# progduino.net
KiCad netlist of a schematic drawn in EAGLE
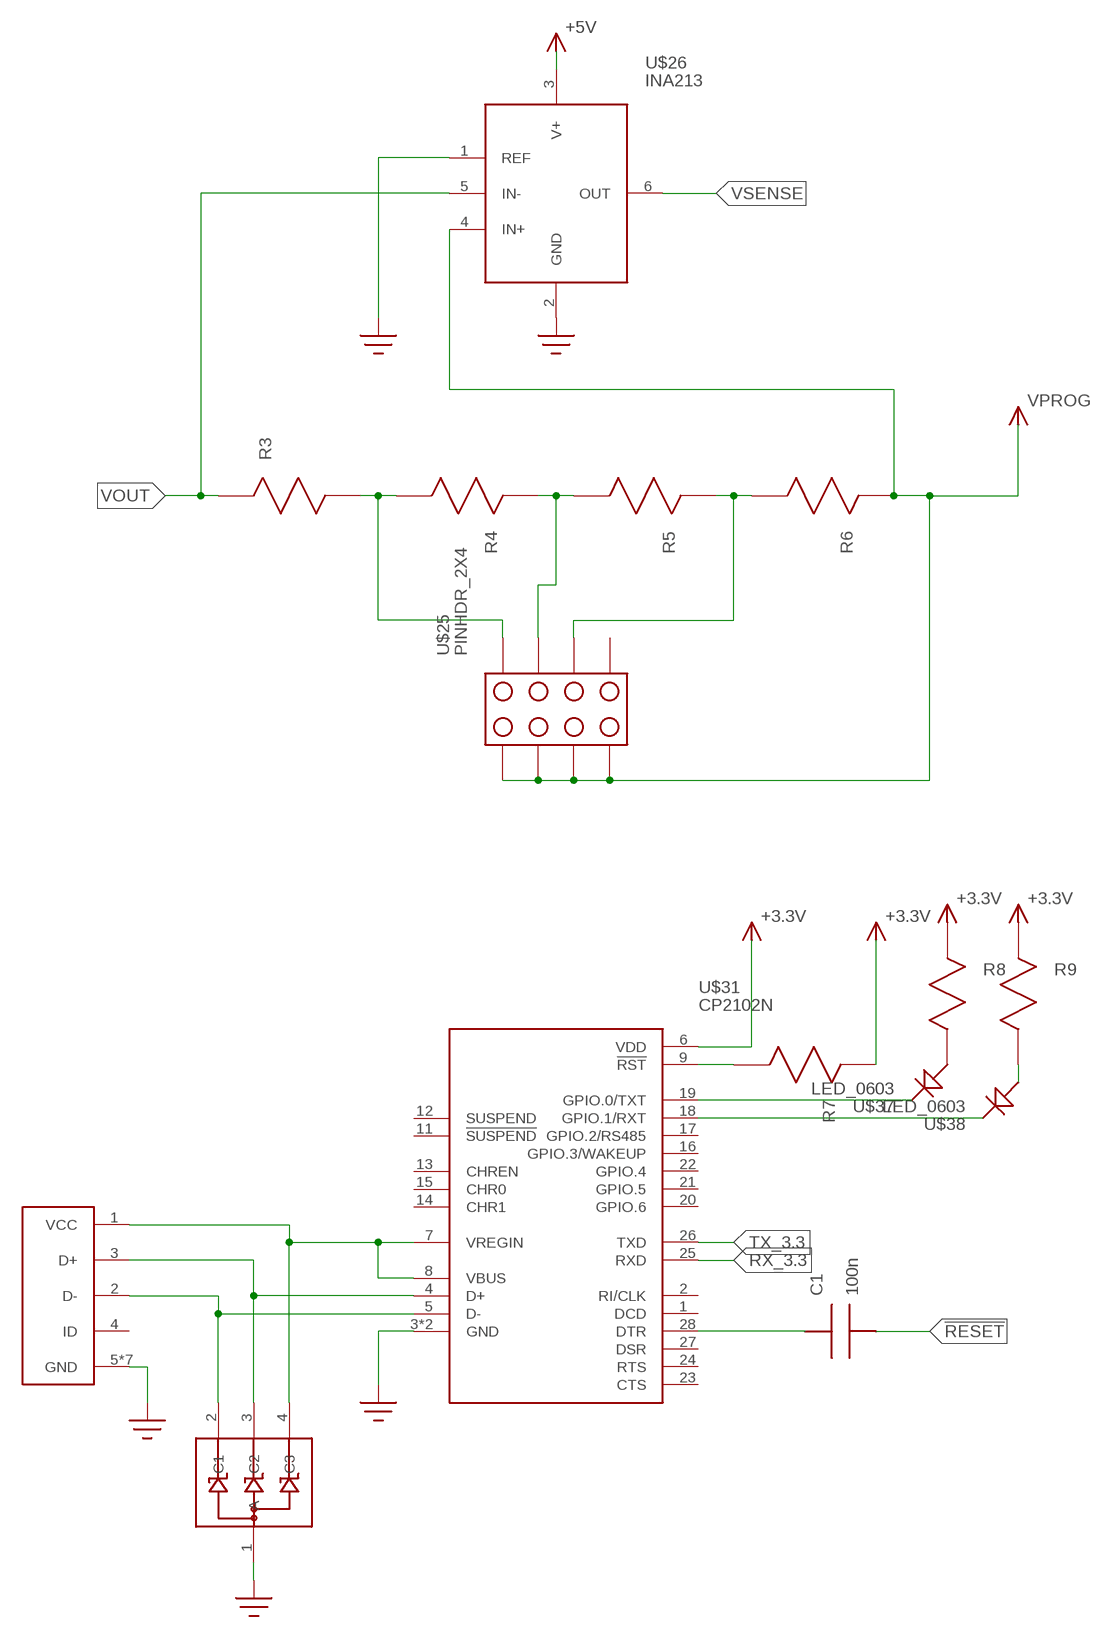
[diagram p0: schematic, sheet 1, part 1 of 2]
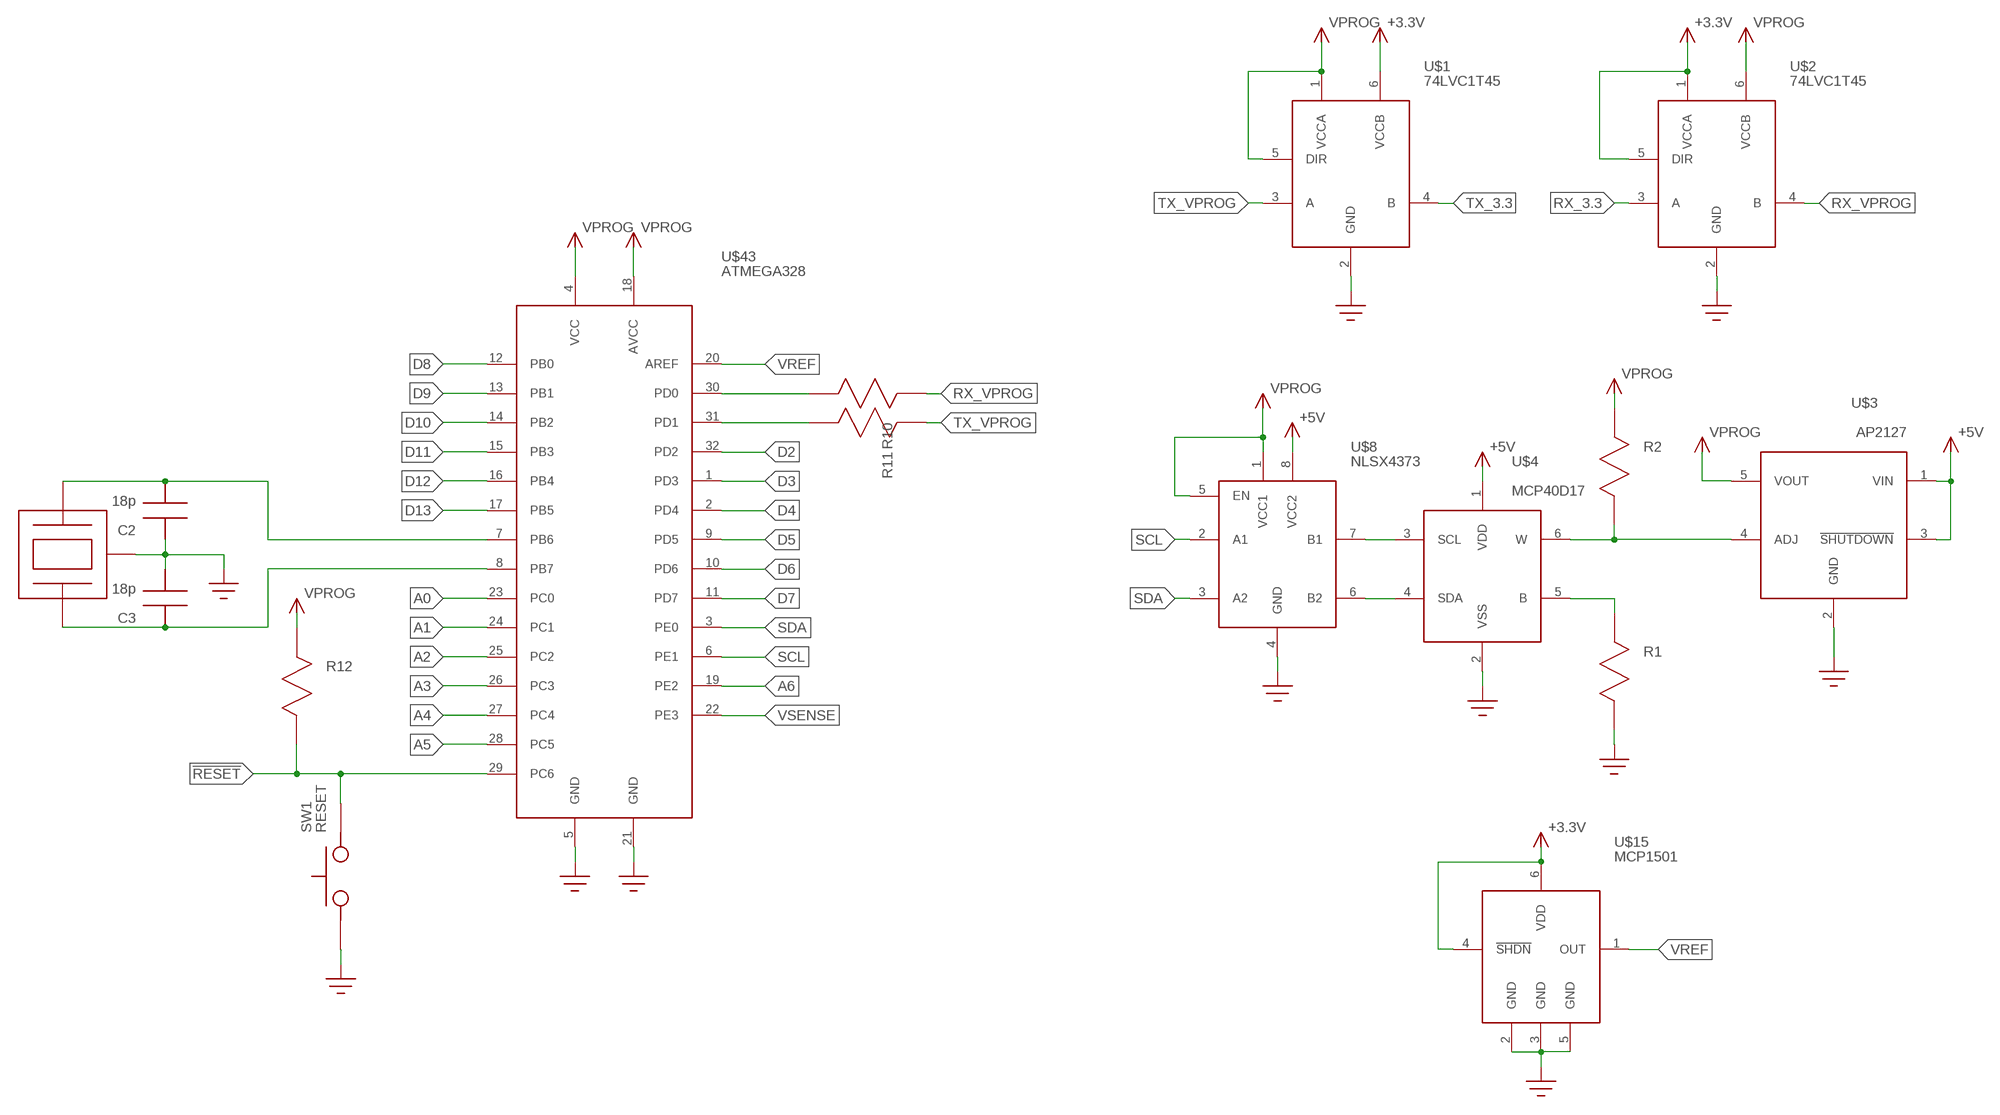
[diagram p1: schematic, sheet 1, part 2 of 2]

(export (version "E")
  (design (tool "Eeschema 10.0.6"))
  (components
    (comp (ref "C1")
      (value "100n")
      (footprint "eagle-import:C0603")
      (libsource (lib "eagle-import") (part "C0603"))
    )
    (comp (ref "C2")
      (value "18p")
      (footprint "eagle-import:C0603")
      (libsource (lib "eagle-import") (part "C0603"))
    )
    (comp (ref "C3")
      (value "18p")
      (footprint "eagle-import:C0603")
      (libsource (lib "eagle-import") (part "C0603"))
    )
    (comp (ref "R1")
      (value "R0603")
      (footprint "eagle-import:R0603")
      (libsource (lib "eagle-import") (part "R0603"))
    )
    (comp (ref "R2")
      (value "R0603")
      (footprint "eagle-import:R0603")
      (libsource (lib "eagle-import") (part "R0603"))
    )
    (comp (ref "R3")
      (value "R0805")
      (footprint "eagle-import:R0805")
      (libsource (lib "eagle-import") (part "R0805"))
    )
    (comp (ref "R4")
      (value "R0805")
      (footprint "eagle-import:R0805")
      (libsource (lib "eagle-import") (part "R0805"))
    )
    (comp (ref "R5")
      (value "R0805")
      (footprint "eagle-import:R0805")
      (libsource (lib "eagle-import") (part "R0805"))
    )
    (comp (ref "R6")
      (value "R0805")
      (footprint "eagle-import:R0805")
      (libsource (lib "eagle-import") (part "R0805"))
    )
    (comp (ref "R7")
      (value "R0603")
      (footprint "eagle-import:R0603")
      (libsource (lib "eagle-import") (part "R0603"))
    )
    (comp (ref "R8")
      (value "R0603")
      (footprint "eagle-import:R0603")
      (libsource (lib "eagle-import") (part "R0603"))
    )
    (comp (ref "R9")
      (value "R0603")
      (footprint "eagle-import:R0603")
      (libsource (lib "eagle-import") (part "R0603"))
    )
    (comp (ref "R10")
      (value "R0603")
      (footprint "eagle-import:R0603")
      (libsource (lib "eagle-import") (part "R0603"))
    )
    (comp (ref "R11")
      (value "R0603")
      (footprint "eagle-import:R0603")
      (libsource (lib "eagle-import") (part "R0603"))
    )
    (comp (ref "R12")
      (value "R0603")
      (footprint "eagle-import:R0603")
      (libsource (lib "eagle-import") (part "R0603"))
    )
    (comp (ref "SW1")
      (value "RESET")
      (footprint "eagle-import:SMD_SWITCH")
      (libsource (lib "eagle-import") (part "SMD_SWITCH"))
    )
    (comp (ref "U$1")
      (value "74LVC1T45")
      (footprint "eagle-import:SOT23-6")
      (libsource (lib "eagle-import") (part "74LVC1T45"))
    )
    (comp (ref "U$2")
      (value "74LVC1T45")
      (footprint "eagle-import:SOT23-6")
      (libsource (lib "eagle-import") (part "74LVC1T45"))
    )
    (comp (ref "U$3")
      (value "AP2127")
      (footprint "eagle-import:SOT23-5")
      (libsource (lib "eagle-import") (part "AP2127"))
    )
    (comp (ref "U$4")
      (value "MCP40D17")
      (footprint "eagle-import:SC70-6")
      (libsource (lib "eagle-import") (part "MCP40D17"))
    )
    (comp (ref "U$8")
      (value "NLSX4373")
      (footprint "eagle-import:SOIC8")
      (libsource (lib "eagle-import") (part "NLSX4373"))
    )
    (comp (ref "U$15")
      (value "MCP1501")
      (footprint "eagle-import:SOT23-6")
      (libsource (lib "eagle-import") (part "MCP1501"))
    )
    (comp (ref "U$25")
      (value "PINHDR_2X4")
      (footprint "eagle-import:PINHDR_2X4")
      (libsource (lib "eagle-import") (part "PINHDR_2X4"))
    )
    (comp (ref "U$26")
      (value "INA213")
      (footprint "eagle-import:SC70-6")
      (libsource (lib "eagle-import") (part "INA213"))
    )
    (comp (ref "U$31")
      (value "CP2102N")
      (footprint "eagle-import:QFN28")
      (libsource (lib "eagle-import") (part "CP2102N"))
    )
    (comp (ref "U$37")
      (value "LED_0603")
      (footprint "eagle-import:LED_0603")
      (libsource (lib "eagle-import") (part "LED_0603"))
    )
    (comp (ref "U$38")
      (value "LED_0603")
      (footprint "eagle-import:LED_0603")
      (libsource (lib "eagle-import") (part "LED_0603"))
    )
    (comp (ref "U$39")
      (value "USB_JACK")
      (footprint "eagle-import:FCI_MICRO_USB")
      (libsource (lib "eagle-import") (part "USB_JACK"))
    )
    (comp (ref "U$40")
      (value "SP0503_TVS")
      (footprint "eagle-import:SOT143")
      (libsource (lib "eagle-import") (part "SP0503_TVS"))
    )
    (comp (ref "U$43")
      (value "ATMEGA328")
      (footprint "eagle-import:TQFP32_7X7")
      (libsource (lib "eagle-import") (part "ATMEGA328"))
    )
    (comp (ref "U$49")
      (value "XTAL")
      (footprint "eagle-import:CRYSTAL_3.2X2.5")
      (libsource (lib "eagle-import") (part "XTAL"))
    )
  )
  (nets
    (net (code "1") (name "+3.3V") (class "Default")
      (node (ref "R7") (pin "P$1") (pinfunction "P$1_P$1") (pintype "bidirectional"))
      (node (ref "R8") (pin "P$1") (pinfunction "P$1_P$1") (pintype "bidirectional"))
      (node (ref "R9") (pin "P$1") (pinfunction "P$1_P$1") (pintype "bidirectional"))
      (node (ref "U$1") (pin "6") (pinfunction "VCCB_6") (pintype "bidirectional"))
      (node (ref "U$15") (pin "4") (pinfunction "~{SHDN}_4") (pintype "bidirectional"))
      (node (ref "U$15") (pin "6") (pinfunction "VDD_6") (pintype "bidirectional"))
      (node (ref "U$2") (pin "1") (pinfunction "VCCA_1") (pintype "bidirectional"))
      (node (ref "U$2") (pin "5") (pinfunction "DIR_5") (pintype "bidirectional"))
      (node (ref "U$31") (pin "6") (pinfunction "VDD_6") (pintype "bidirectional"))
    )
    (net (code "2") (name "+5V") (class "Default")
      (node (ref "U$26") (pin "3") (pinfunction "V+_3") (pintype "bidirectional"))
      (node (ref "U$3") (pin "1") (pinfunction "VIN_1") (pintype "bidirectional"))
      (node (ref "U$3") (pin "3") (pinfunction "~{SHUTDOWN}_3") (pintype "bidirectional"))
      (node (ref "U$4") (pin "1") (pinfunction "VDD_1") (pintype "bidirectional"))
      (node (ref "U$8") (pin "8") (pinfunction "VCC2_8") (pintype "bidirectional"))
    )
    (net (code "3") (name "/~{RESET}") (class "Default")
      (node (ref "C1") (pin "P$2") (pinfunction "P$2_P$2") (pintype "bidirectional"))
      (node (ref "R12") (pin "P$2") (pinfunction "P$2_P$2") (pintype "bidirectional"))
      (node (ref "SW1") (pin "P$3") (pinfunction "P$2_P$3") (pintype "bidirectional"))
      (node (ref "SW1") (pin "P$4") (pinfunction "P$2_P$4") (pintype "bidirectional"))
      (node (ref "U$43") (pin "29") (pinfunction "PC6_29") (pintype "bidirectional"))
    )
    (net (code "4") (name "A0") (class "Default")
      (node (ref "U$43") (pin "23") (pinfunction "PC0_23") (pintype "bidirectional"))
    )
    (net (code "5") (name "A1") (class "Default")
      (node (ref "U$43") (pin "24") (pinfunction "PC1_24") (pintype "bidirectional"))
    )
    (net (code "6") (name "A2") (class "Default")
      (node (ref "U$43") (pin "25") (pinfunction "PC2_25") (pintype "bidirectional"))
    )
    (net (code "7") (name "A3") (class "Default")
      (node (ref "U$43") (pin "26") (pinfunction "PC3_26") (pintype "bidirectional"))
    )
    (net (code "8") (name "A4") (class "Default")
      (node (ref "U$43") (pin "27") (pinfunction "PC4_27") (pintype "bidirectional"))
    )
    (net (code "9") (name "A5") (class "Default")
      (node (ref "U$43") (pin "28") (pinfunction "PC5_28") (pintype "bidirectional"))
    )
    (net (code "10") (name "A6") (class "Default")
      (node (ref "U$43") (pin "19") (pinfunction "PE2_19") (pintype "bidirectional"))
    )
    (net (code "11") (name "D2") (class "Default")
      (node (ref "U$43") (pin "32") (pinfunction "PD2_32") (pintype "bidirectional"))
    )
    (net (code "12") (name "D3") (class "Default")
      (node (ref "U$43") (pin "1") (pinfunction "PD3_1") (pintype "bidirectional"))
    )
    (net (code "13") (name "D4") (class "Default")
      (node (ref "U$43") (pin "2") (pinfunction "PD4_2") (pintype "bidirectional"))
    )
    (net (code "14") (name "D5") (class "Default")
      (node (ref "U$43") (pin "9") (pinfunction "PD5_9") (pintype "bidirectional"))
    )
    (net (code "15") (name "D6") (class "Default")
      (node (ref "U$43") (pin "10") (pinfunction "PD6_10") (pintype "bidirectional"))
    )
    (net (code "16") (name "D7") (class "Default")
      (node (ref "U$43") (pin "11") (pinfunction "PD7_11") (pintype "bidirectional"))
    )
    (net (code "17") (name "D8") (class "Default")
      (node (ref "U$43") (pin "12") (pinfunction "PB0_12") (pintype "bidirectional"))
    )
    (net (code "18") (name "D9") (class "Default")
      (node (ref "U$43") (pin "13") (pinfunction "PB1_13") (pintype "bidirectional"))
    )
    (net (code "19") (name "D10") (class "Default")
      (node (ref "U$43") (pin "14") (pinfunction "PB2_14") (pintype "bidirectional"))
    )
    (net (code "20") (name "D11") (class "Default")
      (node (ref "U$43") (pin "15") (pinfunction "PB3_15") (pintype "bidirectional"))
    )
    (net (code "21") (name "D12") (class "Default")
      (node (ref "U$43") (pin "16") (pinfunction "PB4_16") (pintype "bidirectional"))
    )
    (net (code "22") (name "D13") (class "Default")
      (node (ref "U$43") (pin "17") (pinfunction "PB5_17") (pintype "bidirectional"))
    )
    (net (code "23") (name "GND") (class "Default")
      (node (ref "C2") (pin "P$1") (pinfunction "P$1_P$1") (pintype "bidirectional"))
      (node (ref "C3") (pin "P$2") (pinfunction "P$2_P$2") (pintype "bidirectional"))
      (node (ref "R1") (pin "P$2") (pinfunction "P$2_P$2") (pintype "bidirectional"))
      (node (ref "SW1") (pin "P$1") (pinfunction "P$1_P$1") (pintype "bidirectional"))
      (node (ref "SW1") (pin "P$2") (pinfunction "P$1_P$2") (pintype "bidirectional"))
      (node (ref "U$1") (pin "2") (pinfunction "GND_2") (pintype "bidirectional"))
      (node (ref "U$15") (pin "2") (pinfunction "GND_2") (pintype "bidirectional"))
      (node (ref "U$15") (pin "3") (pinfunction "GND_3") (pintype "bidirectional"))
      (node (ref "U$15") (pin "5") (pinfunction "GND_5") (pintype "bidirectional"))
      (node (ref "U$2") (pin "2") (pinfunction "GND_2") (pintype "bidirectional"))
      (node (ref "U$26") (pin "1") (pinfunction "REF_1") (pintype "bidirectional"))
      (node (ref "U$26") (pin "2") (pinfunction "GND_2") (pintype "bidirectional"))
      (node (ref "U$3") (pin "2") (pinfunction "GND_2") (pintype "bidirectional"))
      (node (ref "U$31") (pin "3") (pinfunction "GND_3") (pintype "bidirectional"))
      (node (ref "U$31") (pin "PAD") (pinfunction "GND_PAD") (pintype "bidirectional"))
      (node (ref "U$39") (pin "5") (pinfunction "GND_5") (pintype "bidirectional"))
      (node (ref "U$39") (pin "GND1") (pinfunction "GND_GND1") (pintype "bidirectional"))
      (node (ref "U$39") (pin "GND2") (pinfunction "GND_GND2") (pintype "bidirectional"))
      (node (ref "U$39") (pin "GND3") (pinfunction "GND_GND3") (pintype "bidirectional"))
      (node (ref "U$39") (pin "GND4") (pinfunction "GND_GND4") (pintype "bidirectional"))
      (node (ref "U$39") (pin "GND5") (pinfunction "GND_GND5") (pintype "bidirectional"))
      (node (ref "U$39") (pin "GND6") (pinfunction "GND_GND6") (pintype "bidirectional"))
      (node (ref "U$4") (pin "2") (pinfunction "VSS_2") (pintype "bidirectional"))
      (node (ref "U$40") (pin "1") (pinfunction "A_1") (pintype "bidirectional"))
      (node (ref "U$43") (pin "21") (pinfunction "GND_21") (pintype "bidirectional"))
      (node (ref "U$43") (pin "5") (pinfunction "GND_5") (pintype "bidirectional"))
      (node (ref "U$49") (pin "P$2") (pinfunction "P$CASE_P$2") (pintype "bidirectional"))
      (node (ref "U$49") (pin "P$4") (pinfunction "P$CASE_P$4") (pintype "bidirectional"))
      (node (ref "U$8") (pin "4") (pinfunction "GND_4") (pintype "bidirectional"))
    )
    (net (code "24") (name "Net-(R3-PadP$2)") (class "Default")
      (node (ref "R3") (pin "P$2") (pinfunction "P$2_P$2") (pintype "bidirectional"))
      (node (ref "R4") (pin "P$2") (pinfunction "P$2_P$2") (pintype "bidirectional"))
      (node (ref "U$25") (pin "8") (pinfunction "8_8") (pintype "bidirectional"))
    )
    (net (code "25") (name "Net-(R4-PadP$1)") (class "Default")
      (node (ref "R4") (pin "P$1") (pinfunction "P$1_P$1") (pintype "bidirectional"))
      (node (ref "R5") (pin "P$2") (pinfunction "P$2_P$2") (pintype "bidirectional"))
      (node (ref "U$25") (pin "7") (pinfunction "7_7") (pintype "bidirectional"))
    )
    (net (code "26") (name "Net-(R5-PadP$1)") (class "Default")
      (node (ref "R5") (pin "P$1") (pinfunction "P$1_P$1") (pintype "bidirectional"))
      (node (ref "R6") (pin "P$2") (pinfunction "P$2_P$2") (pintype "bidirectional"))
      (node (ref "U$25") (pin "6") (pinfunction "6_6") (pintype "bidirectional"))
    )
    (net (code "27") (name "Net-(R8-PadP$2)") (class "Default")
      (node (ref "R8") (pin "P$2") (pinfunction "P$2_P$2") (pintype "bidirectional"))
      (node (ref "U$37") (pin "A") (pinfunction "A_A") (pintype "bidirectional"))
    )
    (net (code "28") (name "Net-(R9-PadP$2)") (class "Default")
      (node (ref "R9") (pin "P$2") (pinfunction "P$2_P$2") (pintype "bidirectional"))
      (node (ref "U$38") (pin "A") (pinfunction "A_A") (pintype "bidirectional"))
    )
    (net (code "29") (name "Net-(U$3-ADJ)") (class "Default")
      (node (ref "R2") (pin "P$2") (pinfunction "P$2_P$2") (pintype "bidirectional"))
      (node (ref "U$3") (pin "4") (pinfunction "ADJ_4") (pintype "bidirectional"))
      (node (ref "U$4") (pin "6") (pinfunction "W_6") (pintype "bidirectional"))
    )
    (net (code "30") (name "Net-(U$4-B)") (class "Default")
      (node (ref "R1") (pin "P$1") (pinfunction "P$1_P$1") (pintype "bidirectional"))
      (node (ref "U$4") (pin "5") (pinfunction "B_5") (pintype "bidirectional"))
    )
    (net (code "31") (name "Net-(U$4-SCL)") (class "Default")
      (node (ref "U$4") (pin "3") (pinfunction "SCL_3") (pintype "bidirectional"))
      (node (ref "U$8") (pin "7") (pinfunction "B1_7") (pintype "bidirectional"))
    )
    (net (code "32") (name "Net-(U$4-SDA)") (class "Default")
      (node (ref "U$4") (pin "4") (pinfunction "SDA_4") (pintype "bidirectional"))
      (node (ref "U$8") (pin "6") (pinfunction "B2_6") (pintype "bidirectional"))
    )
    (net (code "33") (name "Net-(U$31-D+)") (class "Default")
      (node (ref "U$31") (pin "4") (pinfunction "D+_4") (pintype "bidirectional"))
      (node (ref "U$39") (pin "3") (pinfunction "D+_3") (pintype "bidirectional"))
      (node (ref "U$40") (pin "3") (pinfunction "C2_3") (pintype "bidirectional"))
    )
    (net (code "34") (name "Net-(U$31-D-)") (class "Default")
      (node (ref "U$31") (pin "5") (pinfunction "D-_5") (pintype "bidirectional"))
      (node (ref "U$39") (pin "2") (pinfunction "D-_2") (pintype "bidirectional"))
      (node (ref "U$40") (pin "2") (pinfunction "C1_2") (pintype "bidirectional"))
    )
    (net (code "35") (name "Net-(U$31-DTR)") (class "Default")
      (node (ref "C1") (pin "P$1") (pinfunction "P$1_P$1") (pintype "bidirectional"))
      (node (ref "U$31") (pin "28") (pinfunction "DTR_28") (pintype "bidirectional"))
    )
    (net (code "36") (name "Net-(U$31-GPIO.0{slash}TXT)") (class "Default")
      (node (ref "U$31") (pin "19") (pinfunction "GPIO.0/TXT_19") (pintype "bidirectional"))
      (node (ref "U$37") (pin "C") (pinfunction "C_C") (pintype "bidirectional"))
    )
    (net (code "37") (name "Net-(U$31-GPIO.1{slash}RXT)") (class "Default")
      (node (ref "U$31") (pin "18") (pinfunction "GPIO.1/RXT_18") (pintype "bidirectional"))
      (node (ref "U$38") (pin "C") (pinfunction "C_C") (pintype "bidirectional"))
    )
    (net (code "38") (name "Net-(U$31-VBUS)") (class "Default")
      (node (ref "U$31") (pin "7") (pinfunction "VREGIN_7") (pintype "bidirectional"))
      (node (ref "U$31") (pin "8") (pinfunction "VBUS_8") (pintype "bidirectional"))
      (node (ref "U$39") (pin "1") (pinfunction "VCC_1") (pintype "bidirectional"))
      (node (ref "U$40") (pin "4") (pinfunction "C3_4") (pintype "bidirectional"))
    )
    (net (code "39") (name "Net-(U$31-~{RST})") (class "Default")
      (node (ref "R7") (pin "P$2") (pinfunction "P$2_P$2") (pintype "bidirectional"))
      (node (ref "U$31") (pin "9") (pinfunction "~{RST}_9") (pintype "bidirectional"))
    )
    (net (code "40") (name "Net-(U$43-PB6)") (class "Default")
      (node (ref "C2") (pin "P$2") (pinfunction "P$2_P$2") (pintype "bidirectional"))
      (node (ref "U$43") (pin "7") (pinfunction "PB6_7") (pintype "bidirectional"))
      (node (ref "U$49") (pin "P$1") (pinfunction "P$X1_P$1") (pintype "bidirectional"))
    )
    (net (code "41") (name "Net-(U$43-PB7)") (class "Default")
      (node (ref "C3") (pin "P$1") (pinfunction "P$1_P$1") (pintype "bidirectional"))
      (node (ref "U$43") (pin "8") (pinfunction "PB7_8") (pintype "bidirectional"))
      (node (ref "U$49") (pin "P$3") (pinfunction "P$X2_P$3") (pintype "bidirectional"))
    )
    (net (code "42") (name "Net-(U$43-PD0)") (class "Default")
      (node (ref "R10") (pin "P$2") (pinfunction "P$2_P$2") (pintype "bidirectional"))
      (node (ref "U$43") (pin "30") (pinfunction "PD0_30") (pintype "bidirectional"))
    )
    (net (code "43") (name "Net-(U$43-PD1)") (class "Default")
      (node (ref "R11") (pin "P$2") (pinfunction "P$2_P$2") (pintype "bidirectional"))
      (node (ref "U$43") (pin "31") (pinfunction "PD1_31") (pintype "bidirectional"))
    )
    (net (code "44") (name "RX_3.3") (class "Default")
      (node (ref "U$2") (pin "3") (pinfunction "A_3") (pintype "bidirectional"))
      (node (ref "U$31") (pin "25") (pinfunction "RXD_25") (pintype "bidirectional"))
    )
    (net (code "45") (name "RX_VPROG") (class "Default")
      (node (ref "R10") (pin "P$1") (pinfunction "P$1_P$1") (pintype "bidirectional"))
      (node (ref "U$2") (pin "4") (pinfunction "B_4") (pintype "bidirectional"))
    )
    (net (code "46") (name "SCL") (class "Default")
      (node (ref "U$43") (pin "6") (pinfunction "PE1_6") (pintype "bidirectional"))
      (node (ref "U$8") (pin "2") (pinfunction "A1_2") (pintype "bidirectional"))
    )
    (net (code "47") (name "SDA") (class "Default")
      (node (ref "U$43") (pin "3") (pinfunction "PE0_3") (pintype "bidirectional"))
      (node (ref "U$8") (pin "3") (pinfunction "A2_3") (pintype "bidirectional"))
    )
    (net (code "48") (name "TX_3.3") (class "Default")
      (node (ref "U$1") (pin "4") (pinfunction "B_4") (pintype "bidirectional"))
      (node (ref "U$31") (pin "26") (pinfunction "TXD_26") (pintype "bidirectional"))
    )
    (net (code "49") (name "TX_VPROG") (class "Default")
      (node (ref "R11") (pin "P$1") (pinfunction "P$1_P$1") (pintype "bidirectional"))
      (node (ref "U$1") (pin "3") (pinfunction "A_3") (pintype "bidirectional"))
    )
    (net (code "50") (name "VOUT") (class "Default")
      (node (ref "R3") (pin "P$1") (pinfunction "P$1_P$1") (pintype "bidirectional"))
      (node (ref "U$26") (pin "5") (pinfunction "IN-_5") (pintype "bidirectional"))
    )
    (net (code "51") (name "VPROG") (class "Default")
      (node (ref "R12") (pin "P$1") (pinfunction "P$1_P$1") (pintype "bidirectional"))
      (node (ref "R2") (pin "P$1") (pinfunction "P$1_P$1") (pintype "bidirectional"))
      (node (ref "R6") (pin "P$1") (pinfunction "P$1_P$1") (pintype "bidirectional"))
      (node (ref "U$1") (pin "1") (pinfunction "VCCA_1") (pintype "bidirectional"))
      (node (ref "U$1") (pin "5") (pinfunction "DIR_5") (pintype "bidirectional"))
      (node (ref "U$2") (pin "6") (pinfunction "VCCB_6") (pintype "bidirectional"))
      (node (ref "U$25") (pin "1") (pinfunction "1_1") (pintype "bidirectional"))
      (node (ref "U$25") (pin "2") (pinfunction "2_2") (pintype "bidirectional"))
      (node (ref "U$25") (pin "3") (pinfunction "3_3") (pintype "bidirectional"))
      (node (ref "U$25") (pin "4") (pinfunction "4_4") (pintype "bidirectional"))
      (node (ref "U$26") (pin "4") (pinfunction "IN+_4") (pintype "bidirectional"))
      (node (ref "U$3") (pin "5") (pinfunction "VOUT_5") (pintype "bidirectional"))
      (node (ref "U$43") (pin "18") (pinfunction "AVCC_18") (pintype "bidirectional"))
      (node (ref "U$43") (pin "4") (pinfunction "VCC_4") (pintype "bidirectional"))
      (node (ref "U$8") (pin "1") (pinfunction "VCC1_1") (pintype "bidirectional"))
      (node (ref "U$8") (pin "5") (pinfunction "EN_5") (pintype "bidirectional"))
    )
    (net (code "52") (name "VREF") (class "Default")
      (node (ref "U$15") (pin "1") (pinfunction "OUT_1") (pintype "bidirectional"))
      (node (ref "U$43") (pin "20") (pinfunction "AREF_20") (pintype "bidirectional"))
    )
    (net (code "53") (name "VSENSE") (class "Default")
      (node (ref "U$26") (pin "6") (pinfunction "OUT_6") (pintype "bidirectional"))
      (node (ref "U$43") (pin "22") (pinfunction "PE3_22") (pintype "bidirectional"))
    )
    (net (code "54") (name "unconnected-(U$25-Pad5)") (class "Default")
      (node (ref "U$25") (pin "5") (pinfunction "5_5") (pintype "bidirectional"))
    )
    (net (code "55") (name "unconnected-(U$31-CHR0-Pad15)") (class "Default")
      (node (ref "U$31") (pin "15") (pinfunction "CHR0_15") (pintype "bidirectional"))
    )
    (net (code "56") (name "unconnected-(U$31-CHR1-Pad14)") (class "Default")
      (node (ref "U$31") (pin "14") (pinfunction "CHR1_14") (pintype "bidirectional"))
    )
    (net (code "57") (name "unconnected-(U$31-CHREN-Pad13)") (class "Default")
      (node (ref "U$31") (pin "13") (pinfunction "CHREN_13") (pintype "bidirectional"))
    )
    (net (code "58") (name "unconnected-(U$31-CTS-Pad23)") (class "Default")
      (node (ref "U$31") (pin "23") (pinfunction "CTS_23") (pintype "bidirectional"))
    )
    (net (code "59") (name "unconnected-(U$31-DCD-Pad1)") (class "Default")
      (node (ref "U$31") (pin "1") (pinfunction "DCD_1") (pintype "bidirectional"))
    )
    (net (code "60") (name "unconnected-(U$31-DSR-Pad27)") (class "Default")
      (node (ref "U$31") (pin "27") (pinfunction "DSR_27") (pintype "bidirectional"))
    )
    (net (code "61") (name "unconnected-(U$31-GPIO.2{slash}RS485-Pad17)") (class "Default")
      (node (ref "U$31") (pin "17") (pinfunction "GPIO.2/RS485_17") (pintype "bidirectional"))
    )
    (net (code "62") (name "unconnected-(U$31-GPIO.3{slash}WAKEUP-Pad16)") (class "Default")
      (node (ref "U$31") (pin "16") (pinfunction "GPIO.3/WAKEUP_16") (pintype "bidirectional"))
    )
    (net (code "63") (name "unconnected-(U$31-GPIO.4-Pad22)") (class "Default")
      (node (ref "U$31") (pin "22") (pinfunction "GPIO.4_22") (pintype "bidirectional"))
    )
    (net (code "64") (name "unconnected-(U$31-GPIO.5-Pad21)") (class "Default")
      (node (ref "U$31") (pin "21") (pinfunction "GPIO.5_21") (pintype "bidirectional"))
    )
    (net (code "65") (name "unconnected-(U$31-GPIO.6-Pad20)") (class "Default")
      (node (ref "U$31") (pin "20") (pinfunction "GPIO.6_20") (pintype "bidirectional"))
    )
    (net (code "66") (name "unconnected-(U$31-RI{slash}CLK-Pad2)") (class "Default")
      (node (ref "U$31") (pin "2") (pinfunction "RI/CLK_2") (pintype "bidirectional"))
    )
    (net (code "67") (name "unconnected-(U$31-RTS-Pad24)") (class "Default")
      (node (ref "U$31") (pin "24") (pinfunction "RTS_24") (pintype "bidirectional"))
    )
    (net (code "68") (name "unconnected-(U$31-SUSPEND-Pad12)") (class "Default")
      (node (ref "U$31") (pin "12") (pinfunction "SUSPEND_12") (pintype "bidirectional"))
    )
    (net (code "69") (name "unconnected-(U$31-~{SUSPEND}-Pad11)") (class "Default")
      (node (ref "U$31") (pin "11") (pinfunction "~{SUSPEND}_11") (pintype "bidirectional"))
    )
    (net (code "70") (name "unconnected-(U$39-ID-Pad4)") (class "Default")
      (node (ref "U$39") (pin "4") (pinfunction "ID_4") (pintype "bidirectional"))
    )
  )
)
